# PSU_USB_MCU.net
KiCad netlist of a schematic drawn in Altium Designer
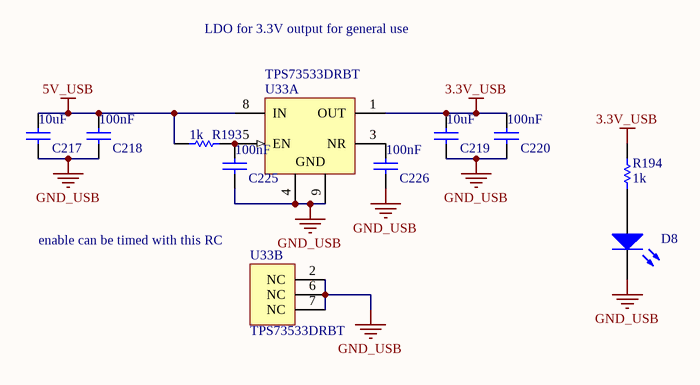
[diagram p0: PSU_USB_MCU.SchDoc]

(export (version "E")
  (design (tool "Eeschema 10.0.6"))
  (components
    (comp (ref "C217")
      (value "10uF")
      (footprint "CAPC0805(2012)145_L")
      (description "0805 (2012 Metric) Chip Capacitor")
      (fields (field (name "Comment") "CAP0805"))
      (libsource (lib "Altium Content Vault") (part "CMP-1590-00003-1"))
    )
    (comp (ref "C218")
      (value "100nF")
      (footprint "CAPC0402(1005)60_L")
      (description "0402 (1005 Metric) Chip Capacitor")
      (fields (field (name "Comment") "CAP0402"))
      (libsource (lib "Altium Content Vault") (part "CMP-1590-00004-1"))
    )
    (comp (ref "C219")
      (value "10uF")
      (footprint "CAPC0805(2012)145_L")
      (description "0805 (2012 Metric) Chip Capacitor")
      (fields (field (name "Comment") "CAP0805"))
      (libsource (lib "Altium Content Vault") (part "CMP-1590-00003-1"))
    )
    (comp (ref "C220")
      (value "100nF")
      (footprint "CAPC0402(1005)60_L")
      (description "0402 (1005 Metric) Chip Capacitor")
      (fields (field (name "Comment") "CAP0402"))
      (libsource (lib "Altium Content Vault") (part "CMP-1590-00004-1"))
    )
    (comp (ref "C225")
      (value "100nF")
      (footprint "CAPC0402(1005)60_L")
      (description "0402 (1005 Metric) Chip Capacitor")
      (fields (field (name "Comment") "CAP0402"))
      (libsource (lib "Altium Content Vault") (part "CMP-1590-00004-1"))
    )
    (comp (ref "C226")
      (value "100nF")
      (footprint "CAPC0402(1005)60_L")
      (description "0402 (1005 Metric) Chip Capacitor")
      (fields (field (name "Comment") "CAP0402"))
      (libsource (lib "Altium Content Vault") (part "CMP-1590-00004-1"))
    )
    (comp (ref "D8")
      (value "Green_LED_150060GS75000")
      (footprint "Green_LED_150060GS75000")
      (description "WURTH ELEKTRONIK  150060GS75000  LED, Green, SMD, 30 mA, 3.2 V, 520 nm")
      (fields
        (field (name "MANUFACTURER PART NUMBER") "150060GS75000")
        (field (name "MANUFACTURER") "WURTH ELEKTRONIK")
      )
      (libsource (lib "Kilian_UCC_Library") (part "Green_LED_150060GS75000"))
    )
    (comp (ref "R193")
      (value "1k")
      (footprint "RESC0402(1005)_L")
      (description "0402 (1005 Metric) Chip Resistor")
      (fields (field (name "Comment") "RES0402"))
      (libsource (lib "Altium Content Vault") (part "CMP-1591-00004-1"))
    )
    (comp (ref "R194")
      (value "1k")
      (footprint "RESC0402(1005)_L")
      (description "0402 (1005 Metric) Chip Resistor")
      (fields (field (name "Comment") "RES0402"))
      (libsource (lib "Altium Content Vault") (part "CMP-1591-00004-1"))
    )
    (comp (ref "U33")
      (value "TPS73533DRBT")
      (footprint "DRB0008A_V")
      (fields (field (name "MANUFACTURER") "Texas Instruments"))
      (libsource (lib "Altium Content Vault") (part "TI-TPS735XXDRB8-1750X1500TP"))
    )
  )
  (nets
    (net (code "1") (name "3.3V_USB") (class "Default")
      (node (ref "C219") (pin "2") (pinfunction "2_2") (pintype "passive"))
      (node (ref "C220") (pin "1") (pinfunction "1_1") (pintype "passive"))
      (node (ref "R194") (pin "1") (pinfunction "1_1") (pintype "passive"))
      (node (ref "U33") (pin "1") (pinfunction "OUT_1") (pintype "power_in"))
    )
    (net (code "2") (name "5V_USB") (class "Default")
      (node (ref "C217") (pin "2") (pinfunction "2_2") (pintype "passive"))
      (node (ref "C218") (pin "1") (pinfunction "1_1") (pintype "passive"))
      (node (ref "R193") (pin "2") (pinfunction "2_2") (pintype "passive"))
      (node (ref "U33") (pin "8") (pinfunction "IN_8") (pintype "power_in"))
    )
    (net (code "3") (name "GND_USB") (class "Default")
      (node (ref "C217") (pin "1") (pinfunction "1_1") (pintype "passive"))
      (node (ref "C218") (pin "2") (pinfunction "2_2") (pintype "passive"))
      (node (ref "C219") (pin "1") (pinfunction "1_1") (pintype "passive"))
      (node (ref "C220") (pin "2") (pinfunction "2_2") (pintype "passive"))
      (node (ref "C225") (pin "2") (pinfunction "2_2") (pintype "passive"))
      (node (ref "C226") (pin "2") (pinfunction "2_2") (pintype "passive"))
      (node (ref "D8") (pin "1") (pinfunction "1_1") (pintype "passive"))
      (node (ref "U33") (pin "2") (pinfunction "NC_2") (pintype "passive"))
      (node (ref "U33") (pin "4") (pinfunction "GND_4") (pintype "power_in"))
      (node (ref "U33") (pin "6") (pinfunction "NC_6") (pintype "passive"))
      (node (ref "U33") (pin "7") (pinfunction "NC_7") (pintype "passive"))
      (node (ref "U33") (pin "9") (pinfunction "GND_9") (pintype "power_in"))
    )
    (net (code "4") (name "Net-(D8-Pad2)") (class "Default")
      (node (ref "D8") (pin "2") (pinfunction "2_2") (pintype "passive"))
      (node (ref "R194") (pin "2") (pinfunction "2_2") (pintype "passive"))
    )
    (net (code "5") (name "Net-(U33A-EN)") (class "Default")
      (node (ref "C225") (pin "1") (pinfunction "1_1") (pintype "passive"))
      (node (ref "R193") (pin "1") (pinfunction "1_1") (pintype "passive"))
      (node (ref "U33") (pin "5") (pinfunction "EN_5") (pintype "input"))
    )
    (net (code "6") (name "Net-(U33A-NR)") (class "Default")
      (node (ref "C226") (pin "1") (pinfunction "1_1") (pintype "passive"))
      (node (ref "U33") (pin "3") (pinfunction "NR_3") (pintype "passive"))
    )
  )
)
